# Sheet1.net
KiCad netlist of a schematic drawn in Altium Designer
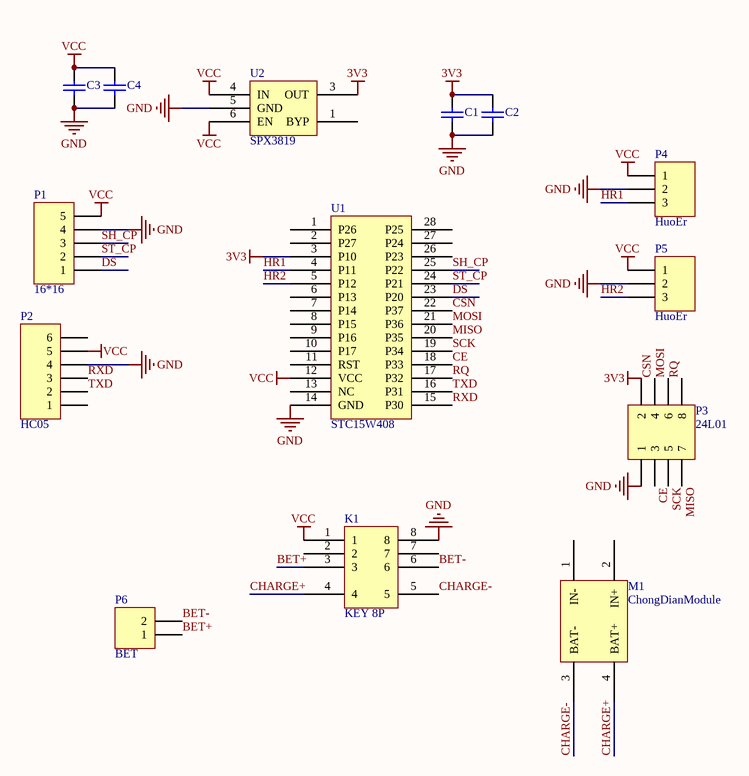
[diagram p0: Sheet1.SchDoc]

(export (version "E")
  (design (tool "Eeschema 10.0.6"))
  (components
    (comp (ref "C1")
      (value "Cap")
      (footprint "C0805")
      (description "Capacitor")
      (fields (field (name "PUBLISHER") "Altium Limited"))
      (libsource (lib "Miscellaneous Devices") (part "Cap"))
    )
    (comp (ref "C2")
      (value "Cap")
      (footprint "C0805")
      (description "Capacitor")
      (fields (field (name "PUBLISHER") "Altium Limited"))
      (libsource (lib "Miscellaneous Devices") (part "Cap"))
    )
    (comp (ref "C3")
      (value "Cap")
      (footprint "C0805")
      (description "Capacitor")
      (fields (field (name "PUBLISHER") "Altium Limited"))
      (libsource (lib "Miscellaneous Devices") (part "Cap"))
    )
    (comp (ref "C4")
      (value "Cap")
      (footprint "C0805")
      (description "Capacitor")
      (fields (field (name "PUBLISHER") "Altium Limited"))
      (libsource (lib "Miscellaneous Devices") (part "Cap"))
    )
    (comp (ref "K1") (value "KEY 8P") (footprint "key 8p") (libsource (lib "MY_SCH_LIB") (part "KEY 8P")))
    (comp (ref "M1")
      (value "ChongDianModule")
      (footprint "ChongDianModule")
      (libsource (lib "MY_SCH_LIB") (part "ChongDianModule"))
    )
    (comp (ref "P1")
      (value "16*16")
      (footprint "HDR1X5")
      (description "Header, 5-Pin")
      (fields (field (name "PUBLISHER") "Altium Limited"))
      (libsource (lib "Miscellaneous Connectors") (part "Header 5"))
    )
    (comp (ref "P2")
      (value "HC05")
      (footprint "HDR1X6")
      (description "Header, 6-Pin")
      (fields (field (name "PUBLISHER") "Altium Limited"))
      (libsource (lib "Miscellaneous Connectors") (part "Header 6"))
    )
    (comp (ref "P3")
      (value "24L01")
      (footprint "HDR2X4")
      (description "Header, 4-Pin, Dual row")
      (fields (field (name "PUBLISHER") "Altium Limited"))
      (libsource (lib "Miscellaneous Connectors") (part "Header 4X2"))
    )
    (comp (ref "P4")
      (value "HuoEr")
      (footprint "HDR1X3")
      (description "Header, 3-Pin")
      (fields (field (name "PUBLISHER") "Altium Limited"))
      (libsource (lib "Miscellaneous Connectors") (part "Header 3"))
    )
    (comp (ref "P5")
      (value "HuoEr")
      (footprint "HDR1X3")
      (description "Header, 3-Pin")
      (fields (field (name "PUBLISHER") "Altium Limited"))
      (libsource (lib "Miscellaneous Connectors") (part "Header 3"))
    )
    (comp (ref "P6")
      (value "BET")
      (footprint "HDR1X2")
      (description "Header, 2-Pin")
      (fields (field (name "PUBLISHER") "Altium Limited"))
      (libsource (lib "Miscellaneous Connectors") (part "Header 2"))
    )
    (comp (ref "U1")
      (value "STC15W408")
      (footprint "SOP28")
      (libsource (lib "MY_SCH_LIB") (part "STC15W408"))
    )
    (comp (ref "U2") (value "SPX3819") (footprint "SOP5(6)") (libsource (lib "MY_SCH_LIB") (part "SPX3819")))
  )
  (nets
    (net (code "1") (name "/BET+") (class "Default")
      (node (ref "K1") (pin "3") (pinfunction "3_3") (pintype "passive"))
      (node (ref "P6") (pin "1") (pinfunction "1_1") (pintype "passive"))
    )
    (net (code "2") (name "/BET-") (class "Default")
      (node (ref "K1") (pin "6") (pinfunction "6_6") (pintype "passive"))
      (node (ref "P6") (pin "2") (pinfunction "2_2") (pintype "passive"))
    )
    (net (code "3") (name "/CE") (class "Default")
      (node (ref "P3") (pin "3") (pinfunction "3_3") (pintype "passive"))
      (node (ref "U1") (pin "18") (pinfunction "P33_18") (pintype "passive"))
    )
    (net (code "4") (name "/CHARGE+") (class "Default")
      (node (ref "K1") (pin "4") (pinfunction "4_4") (pintype "passive"))
      (node (ref "M1") (pin "4") (pinfunction "BAT+_4") (pintype "passive"))
    )
    (net (code "5") (name "/CHARGE-") (class "Default")
      (node (ref "K1") (pin "5") (pinfunction "5_5") (pintype "passive"))
      (node (ref "M1") (pin "3") (pinfunction "BAT-_3") (pintype "passive"))
    )
    (net (code "6") (name "/CSN") (class "Default")
      (node (ref "P3") (pin "4") (pinfunction "4_4") (pintype "passive"))
      (node (ref "U1") (pin "22") (pinfunction "P37_22") (pintype "passive"))
    )
    (net (code "7") (name "/DS") (class "Default")
      (node (ref "P1") (pin "1") (pinfunction "1_1") (pintype "passive"))
      (node (ref "U1") (pin "23") (pinfunction "P20_23") (pintype "passive"))
    )
    (net (code "8") (name "/HR1") (class "Default")
      (node (ref "P4") (pin "3") (pinfunction "3_3") (pintype "passive"))
      (node (ref "U1") (pin "4") (pinfunction "P11_4") (pintype "passive"))
    )
    (net (code "9") (name "/HR2") (class "Default")
      (node (ref "P5") (pin "3") (pinfunction "3_3") (pintype "passive"))
      (node (ref "U1") (pin "5") (pinfunction "P12_5") (pintype "passive"))
    )
    (net (code "10") (name "/MISO") (class "Default")
      (node (ref "P3") (pin "7") (pinfunction "7_7") (pintype "passive"))
      (node (ref "U1") (pin "20") (pinfunction "P35_20") (pintype "passive"))
    )
    (net (code "11") (name "/MOSI") (class "Default")
      (node (ref "P3") (pin "6") (pinfunction "6_6") (pintype "passive"))
      (node (ref "U1") (pin "21") (pinfunction "P36_21") (pintype "passive"))
    )
    (net (code "12") (name "/RQ") (class "Default")
      (node (ref "P3") (pin "8") (pinfunction "8_8") (pintype "passive"))
      (node (ref "U1") (pin "17") (pinfunction "P32_17") (pintype "passive"))
    )
    (net (code "13") (name "/RXD") (class "Default")
      (node (ref "P2") (pin "3") (pinfunction "3_3") (pintype "passive"))
      (node (ref "U1") (pin "15") (pinfunction "P30_15") (pintype "passive"))
    )
    (net (code "14") (name "/SCK") (class "Default")
      (node (ref "P3") (pin "5") (pinfunction "5_5") (pintype "passive"))
      (node (ref "U1") (pin "19") (pinfunction "P34_19") (pintype "passive"))
    )
    (net (code "15") (name "/SH_CP") (class "Default")
      (node (ref "P1") (pin "3") (pinfunction "3_3") (pintype "passive"))
      (node (ref "U1") (pin "25") (pinfunction "P22_25") (pintype "passive"))
    )
    (net (code "16") (name "/ST_CP") (class "Default")
      (node (ref "P1") (pin "2") (pinfunction "2_2") (pintype "passive"))
      (node (ref "U1") (pin "24") (pinfunction "P21_24") (pintype "passive"))
    )
    (net (code "17") (name "/TXD") (class "Default")
      (node (ref "P2") (pin "2") (pinfunction "2_2") (pintype "passive"))
      (node (ref "U1") (pin "16") (pinfunction "P31_16") (pintype "passive"))
    )
    (net (code "18") (name "3V3") (class "Default")
      (node (ref "C1") (pin "2") (pinfunction "2_2") (pintype "passive"))
      (node (ref "C2") (pin "2") (pinfunction "2_2") (pintype "passive"))
      (node (ref "P3") (pin "2") (pinfunction "2_2") (pintype "passive"))
      (node (ref "U1") (pin "3") (pinfunction "P10_3") (pintype "passive"))
      (node (ref "U2") (pin "3") (pinfunction "OUT_3") (pintype "passive"))
    )
    (net (code "19") (name "GND") (class "Default")
      (node (ref "C1") (pin "1") (pinfunction "1_1") (pintype "passive"))
      (node (ref "C2") (pin "1") (pinfunction "1_1") (pintype "passive"))
      (node (ref "C3") (pin "1") (pinfunction "1_1") (pintype "passive"))
      (node (ref "C4") (pin "1") (pinfunction "1_1") (pintype "passive"))
      (node (ref "K1") (pin "8") (pinfunction "8_8") (pintype "passive"))
      (node (ref "P1") (pin "4") (pinfunction "4_4") (pintype "passive"))
      (node (ref "P2") (pin "4") (pinfunction "4_4") (pintype "passive"))
      (node (ref "P3") (pin "1") (pinfunction "1_1") (pintype "passive"))
      (node (ref "P4") (pin "2") (pinfunction "2_2") (pintype "passive"))
      (node (ref "P5") (pin "2") (pinfunction "2_2") (pintype "passive"))
      (node (ref "U1") (pin "14") (pinfunction "GND_14") (pintype "passive"))
      (node (ref "U2") (pin "5") (pinfunction "GND_5") (pintype "passive"))
    )
    (net (code "20") (name "VCC") (class "Default")
      (node (ref "C3") (pin "2") (pinfunction "2_2") (pintype "passive"))
      (node (ref "C4") (pin "2") (pinfunction "2_2") (pintype "passive"))
      (node (ref "K1") (pin "1") (pinfunction "1_1") (pintype "passive"))
      (node (ref "P1") (pin "5") (pinfunction "5_5") (pintype "passive"))
      (node (ref "P2") (pin "5") (pinfunction "5_5") (pintype "passive"))
      (node (ref "P4") (pin "1") (pinfunction "1_1") (pintype "passive"))
      (node (ref "P5") (pin "1") (pinfunction "1_1") (pintype "passive"))
      (node (ref "U1") (pin "12") (pinfunction "VCC_12") (pintype "passive"))
      (node (ref "U2") (pin "4") (pinfunction "IN_4") (pintype "passive"))
      (node (ref "U2") (pin "6") (pinfunction "EN_6") (pintype "passive"))
    )
    (net (code "21") (name "unconnected-(K1-Pad2)") (class "Default")
      (node (ref "K1") (pin "2") (pinfunction "2_2") (pintype "passive"))
    )
    (net (code "22") (name "unconnected-(K1-Pad7)") (class "Default")
      (node (ref "K1") (pin "7") (pinfunction "7_7") (pintype "passive"))
    )
    (net (code "23") (name "unconnected-(M1-IN+-Pad2)") (class "Default")
      (node (ref "M1") (pin "2") (pinfunction "IN+_2") (pintype "passive"))
    )
    (net (code "24") (name "unconnected-(M1-IN--Pad1)") (class "Default")
      (node (ref "M1") (pin "1") (pinfunction "IN-_1") (pintype "passive"))
    )
    (net (code "25") (name "unconnected-(P2-Pad1)") (class "Default")
      (node (ref "P2") (pin "1") (pinfunction "1_1") (pintype "passive"))
    )
    (net (code "26") (name "unconnected-(P2-Pad6)") (class "Default")
      (node (ref "P2") (pin "6") (pinfunction "6_6") (pintype "passive"))
    )
    (net (code "27") (name "unconnected-(U1-NC-Pad13)") (class "Default")
      (node (ref "U1") (pin "13") (pinfunction "NC_13") (pintype "passive"))
    )
    (net (code "28") (name "unconnected-(U1-P13-Pad6)") (class "Default")
      (node (ref "U1") (pin "6") (pinfunction "P13_6") (pintype "passive"))
    )
    (net (code "29") (name "unconnected-(U1-P14-Pad7)") (class "Default")
      (node (ref "U1") (pin "7") (pinfunction "P14_7") (pintype "passive"))
    )
    (net (code "30") (name "unconnected-(U1-P15-Pad8)") (class "Default")
      (node (ref "U1") (pin "8") (pinfunction "P15_8") (pintype "passive"))
    )
    (net (code "31") (name "unconnected-(U1-P16-Pad9)") (class "Default")
      (node (ref "U1") (pin "9") (pinfunction "P16_9") (pintype "passive"))
    )
    (net (code "32") (name "unconnected-(U1-P17-Pad10)") (class "Default")
      (node (ref "U1") (pin "10") (pinfunction "P17_10") (pintype "passive"))
    )
    (net (code "33") (name "unconnected-(U1-P23-Pad26)") (class "Default")
      (node (ref "U1") (pin "26") (pinfunction "P23_26") (pintype "passive"))
    )
    (net (code "34") (name "unconnected-(U1-P24-Pad27)") (class "Default")
      (node (ref "U1") (pin "27") (pinfunction "P24_27") (pintype "passive"))
    )
    (net (code "35") (name "unconnected-(U1-P25-Pad28)") (class "Default")
      (node (ref "U1") (pin "28") (pinfunction "P25_28") (pintype "passive"))
    )
    (net (code "36") (name "unconnected-(U1-P26-Pad1)") (class "Default")
      (node (ref "U1") (pin "1") (pinfunction "P26_1") (pintype "passive"))
    )
    (net (code "37") (name "unconnected-(U1-P27-Pad2)") (class "Default")
      (node (ref "U1") (pin "2") (pinfunction "P27_2") (pintype "passive"))
    )
    (net (code "38") (name "unconnected-(U1-RST-Pad11)") (class "Default")
      (node (ref "U1") (pin "11") (pinfunction "RST_11") (pintype "passive"))
    )
    (net (code "39") (name "unconnected-(U2-BYP-Pad1)") (class "Default")
      (node (ref "U2") (pin "1") (pinfunction "BYP_1") (pintype "passive"))
    )
  )
)
